# 1-Schematic_Automatic_watering_v1_1.net
KiCad netlist of a schematic drawn in EasyEDA
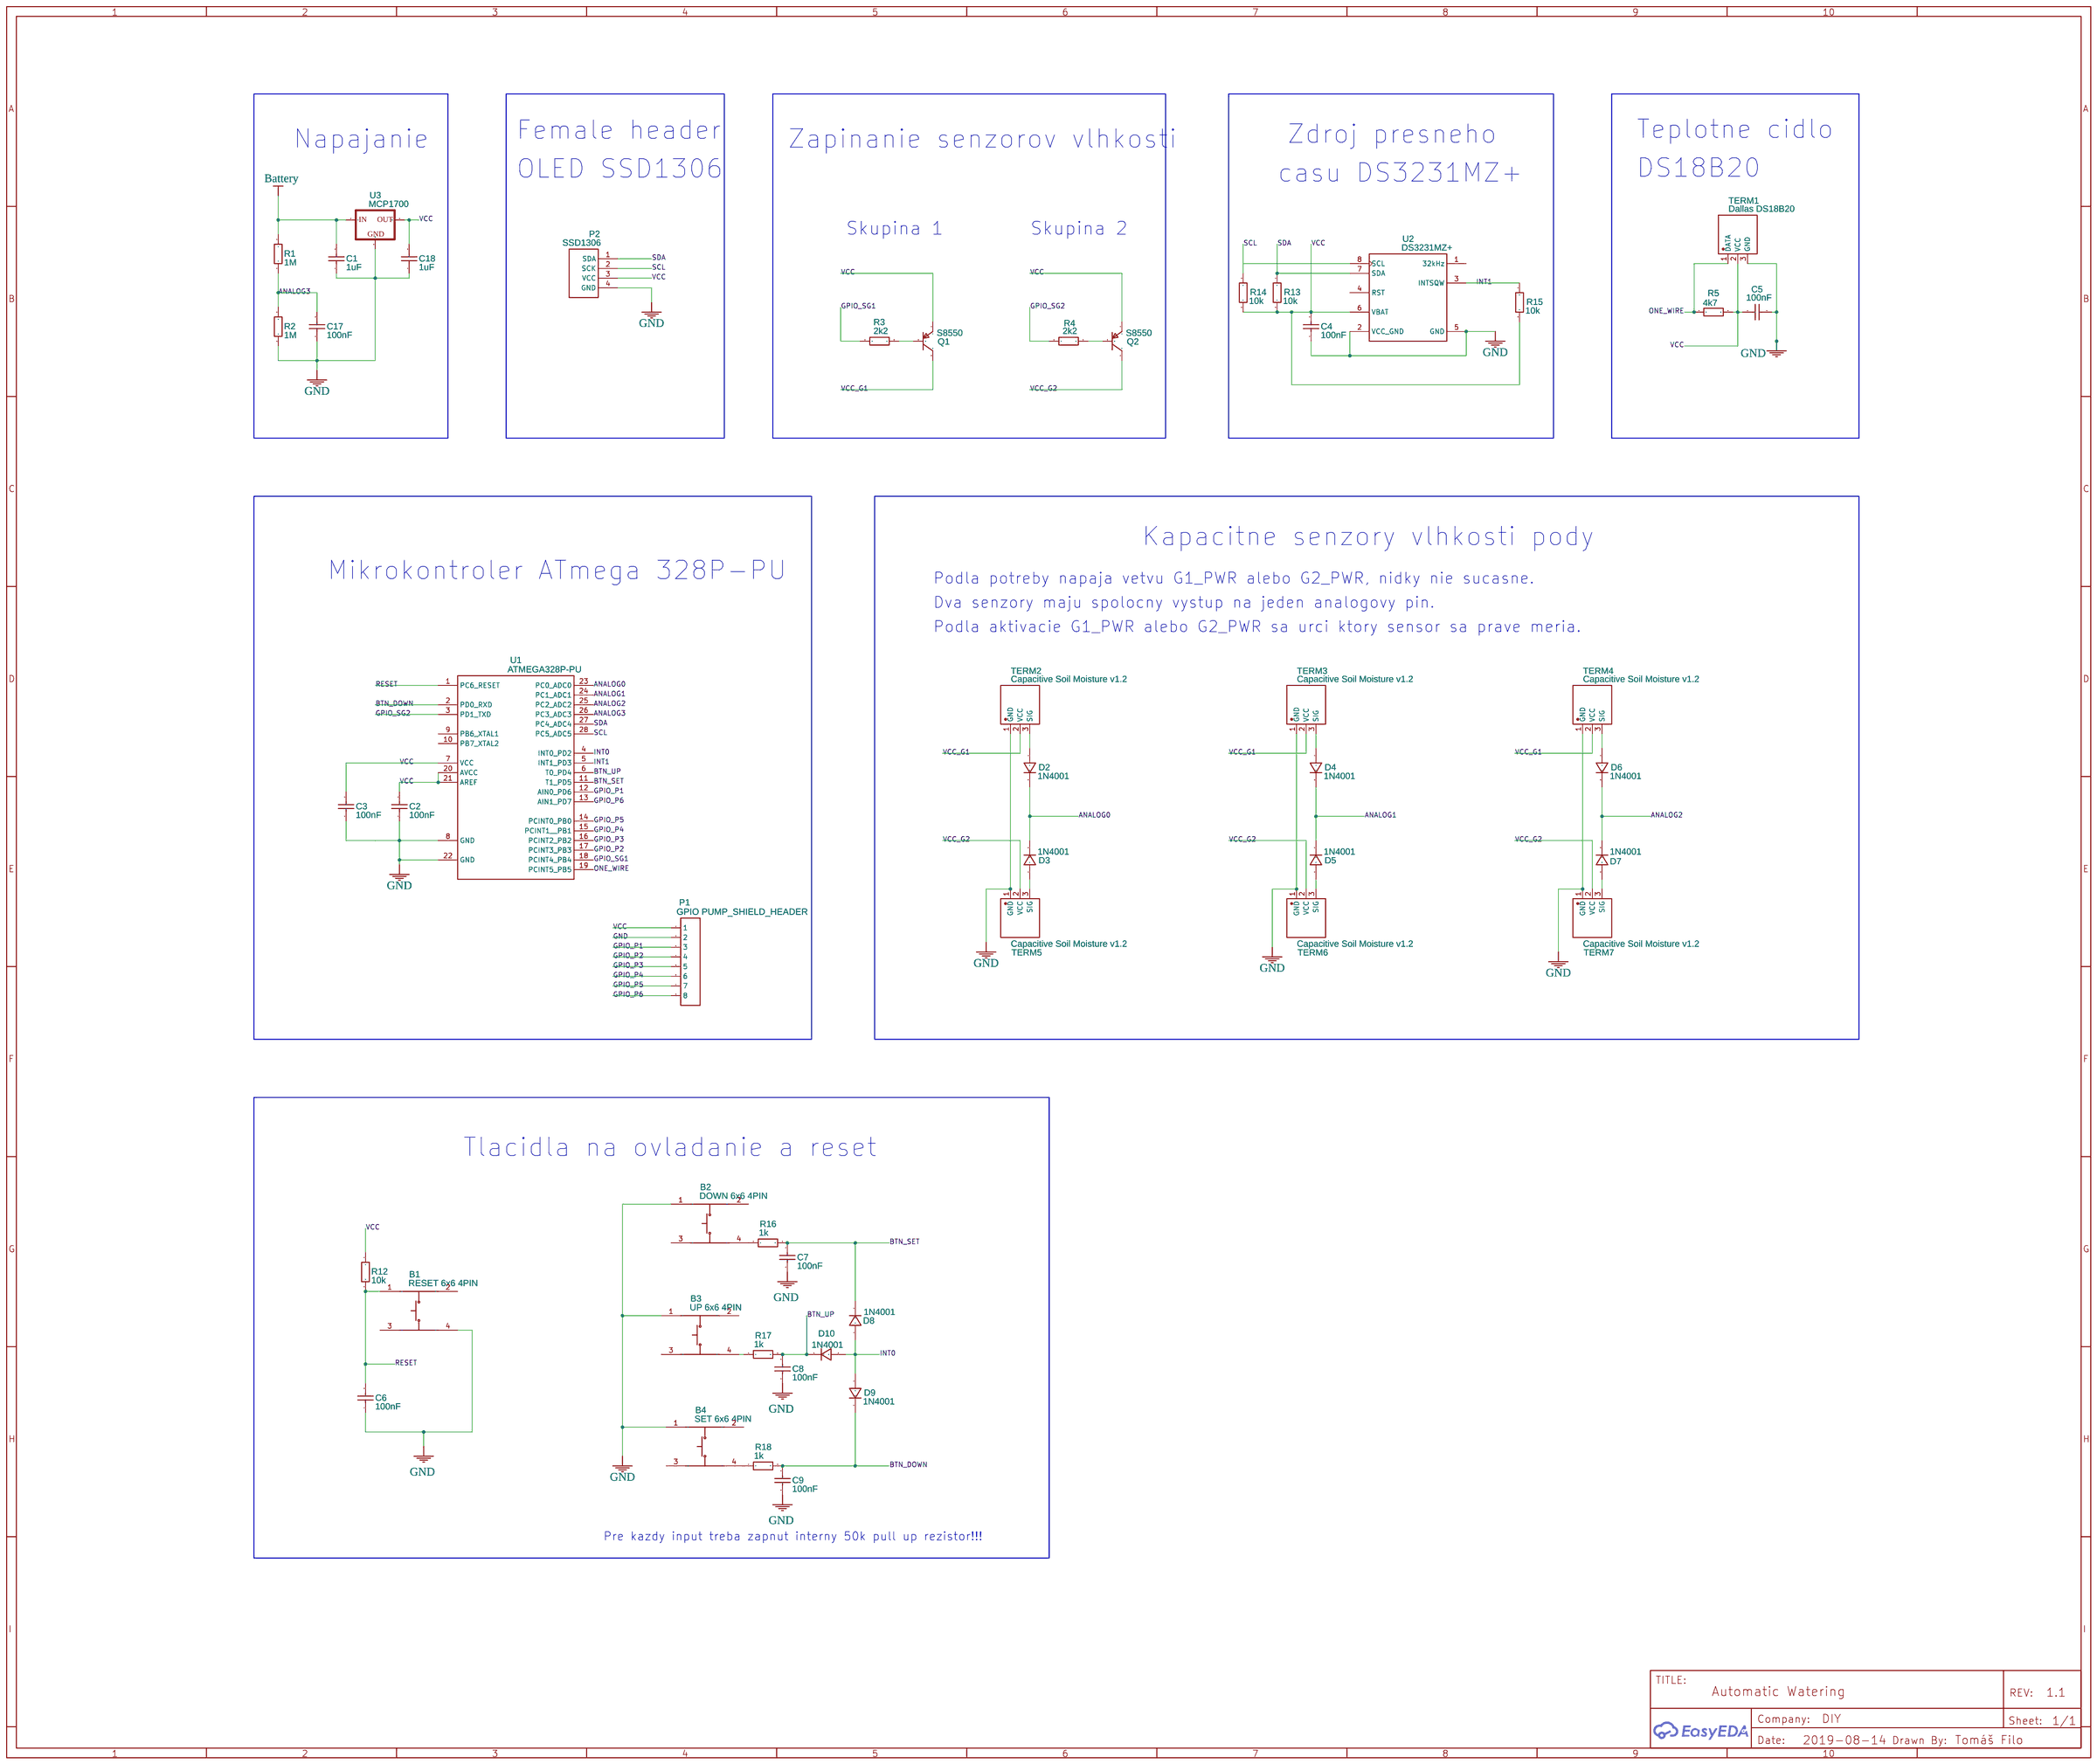
[diagram p0: schematic sheet]

(export (version "E")
  (design (tool "Eeschema 10.0.6"))
  (components
    (comp (ref "B1")
      (value "RESET 6x6 4PIN")
      (fields
        (field (name "BOM_Manufacturer Part") "TC-1102-C-E-B")
        (field (name "BOM_Supplier Part") "C381011")
      )
      (libsource (lib "") (part "Unknown_425_1345"))
    )
    (comp (ref "B2")
      (value "DOWN 6x6 4PIN")
      (fields
        (field (name "BOM_Manufacturer Part") "TC-1102-C-E-B")
        (field (name "BOM_Supplier Part") "C381011")
      )
      (libsource (lib "") (part "Unknown_725_1255"))
    )
    (comp (ref "B3")
      (value "UP 6x6 4PIN")
      (fields
        (field (name "BOM_Manufacturer Part") "TC-1102-C-E-B")
        (field (name "BOM_Supplier Part") "C381011")
      )
      (libsource (lib "") (part "Unknown_715_1370"))
    )
    (comp (ref "B4")
      (value "SET 6x6 4PIN")
      (fields
        (field (name "BOM_Manufacturer Part") "TC-1102-C-E-B")
        (field (name "BOM_Supplier Part") "C381011")
      )
      (libsource (lib "") (part "Unknown_720_1485"))
    )
    (comp (ref "C1")
      (value "1uF")
      (fields
        (field (name "BOM_Manufacturer Part") "CD1H224KC9BER1E000")
        (field (name "BOM_Supplier Part") "C263191")
      )
      (libsource (lib "") (part "CD1H224KC9BER1E000_1"))
    )
    (comp (ref "C2")
      (value "100nF")
      (fields
        (field (name "BOM_Manufacturer Part") "CD1H224KC9BER1E000")
        (field (name "BOM_Supplier Part") "C263191")
      )
      (libsource (lib "") (part "CD1H224KC9BER1E000_1"))
    )
    (comp (ref "C3")
      (value "100nF")
      (fields
        (field (name "BOM_Manufacturer Part") "CD1H224KC9BER1E000")
        (field (name "BOM_Supplier Part") "C263191")
      )
      (libsource (lib "") (part "CD1H224KC9BER1E000_1"))
    )
    (comp (ref "C4")
      (value "100nF")
      (fields
        (field (name "BOM_Manufacturer Part") "CD1H224KC9BER1E000")
        (field (name "BOM_Supplier Part") "C263191")
      )
      (libsource (lib "") (part "CD1H224KC9BER1E000_1"))
    )
    (comp (ref "C5")
      (value "100nF")
      (fields
        (field (name "BOM_Manufacturer Part") "CD1H224KC9BER1E000")
        (field (name "BOM_Supplier Part") "C263191")
      )
      (libsource (lib "") (part "CD1H224KC9BER1E000"))
    )
    (comp (ref "C6")
      (value "100nF")
      (fields
        (field (name "BOM_Manufacturer Part") "CD1H224KC9BER1E000")
        (field (name "BOM_Supplier Part") "C263191")
      )
      (libsource (lib "") (part "CD1H224KC9BER1E000_1"))
    )
    (comp (ref "C7")
      (value "100nF")
      (fields
        (field (name "BOM_Manufacturer Part") "CD1H224KC9BER1E000")
        (field (name "BOM_Supplier Part") "C263191")
      )
      (libsource (lib "") (part "CD1H224KC9BER1E000_1"))
    )
    (comp (ref "C8")
      (value "100nF")
      (fields
        (field (name "BOM_Manufacturer Part") "CD1H224KC9BER1E000")
        (field (name "BOM_Supplier Part") "C263191")
      )
      (libsource (lib "") (part "CD1H224KC9BER1E000_1"))
    )
    (comp (ref "C9")
      (value "100nF")
      (fields
        (field (name "BOM_Manufacturer Part") "CD1H224KC9BER1E000")
        (field (name "BOM_Supplier Part") "C263191")
      )
      (libsource (lib "") (part "CD1H224KC9BER1E000_1"))
    )
    (comp (ref "C17")
      (value "100nF")
      (fields
        (field (name "BOM_Manufacturer Part") "CD1H224KC9BER1E000")
        (field (name "BOM_Supplier Part") "C263191")
      )
      (libsource (lib "") (part "CD1H224KC9BER1E000_1"))
    )
    (comp (ref "C18")
      (value "1uF")
      (fields
        (field (name "BOM_Manufacturer Part") "CD1H224KC9BER1E000")
        (field (name "BOM_Supplier Part") "C263191")
      )
      (libsource (lib "") (part "CD1H224KC9BER1E000_1"))
    )
    (comp (ref "D2")
      (value "1N4001")
      (fields (field (name "BOM_Supplier Part") "C169150"))
      (libsource (lib "") (part "Unknown_1055_785"))
    )
    (comp (ref "D3")
      (value "1N4001")
      (fields (field (name "BOM_Supplier Part") "C169150"))
      (libsource (lib "") (part "Unknown_1055_880"))
    )
    (comp (ref "D4")
      (value "1N4001")
      (fields (field (name "BOM_Supplier Part") "C169150"))
      (libsource (lib "") (part "Unknown_1350_785"))
    )
    (comp (ref "D5")
      (value "1N4001")
      (fields (field (name "BOM_Supplier Part") "C169150"))
      (libsource (lib "") (part "Unknown_1350_880"))
    )
    (comp (ref "D6")
      (value "1N4001")
      (fields (field (name "BOM_Supplier Part") "C169150"))
      (libsource (lib "") (part "Unknown_1645_785"))
    )
    (comp (ref "D7")
      (value "1N4001")
      (fields (field (name "BOM_Supplier Part") "C169150"))
      (libsource (lib "") (part "Unknown_1645_880"))
    )
    (comp (ref "D8")
      (value "1N4001")
      (fields (field (name "BOM_Supplier Part") "C169150"))
      (libsource (lib "") (part "Unknown_875_1355"))
    )
    (comp (ref "D9")
      (value "1N4001")
      (fields (field (name "BOM_Supplier Part") "C169150"))
      (libsource (lib "") (part "Unknown_875_1430"))
    )
    (comp (ref "D10")
      (value "1N4001")
      (fields (field (name "BOM_Supplier Part") "C169150"))
      (libsource (lib "") (part "Unknown_845_1390"))
    )
    (comp (ref "P1")
      (value "GPIO PUMP_SHIELD_HEADER")
      (fields
        (field (name "BOM_Manufacturer Part") "Female headerHDR1X8-2.54")
        (field (name "BOM_Supplier Part") "C27438")
      )
      (libsource (lib "") (part "Unknown_700_985"))
    )
    (comp (ref "P2")
      (value "SSD1306")
      (fields
        (field (name "BOM_Manufacturer Part") "220S-1*4P H=8.5MM Ytype Gold-plated")
        (field (name "BOM_Supplier Part") "C124413")
      )
      (libsource (lib "") (part "Unknown_605_275"))
    )
    (comp (ref "Q1")
      (value "S8550")
      (fields (field (name "BOM_Manufacturer Part") "SS8550CTA") (field (name "BOM_Supplier Part") "C327518"))
      (libsource (lib "") (part "Unknown_945_345"))
    )
    (comp (ref "Q2")
      (value "S8550")
      (fields (field (name "BOM_Manufacturer Part") "SS8550CTA") (field (name "BOM_Supplier Part") "C327518"))
      (libsource (lib "") (part "Unknown_1140_345"))
    )
    (comp (ref "R1")
      (value "1M")
      (fields (field (name "BOM_Supplier Part") "C119320"))
      (libsource (lib "") (part "MF1/4W-680Ω±1% T52"))
    )
    (comp (ref "R2")
      (value "1M")
      (fields (field (name "BOM_Supplier Part") "C119320"))
      (libsource (lib "") (part "MF1/4W-680Ω±1% T52"))
    )
    (comp (ref "R3")
      (value "2k2")
      (fields (field (name "BOM_Supplier Part") "C119313"))
      (libsource (lib "") (part "MF1/4W-330Ω±1% T52_1"))
    )
    (comp (ref "R4")
      (value "2k2")
      (fields (field (name "BOM_Supplier Part") "C119313"))
      (libsource (lib "") (part "MF1/4W-330Ω±1% T52_1"))
    )
    (comp (ref "R5")
      (value "4k7")
      (fields (field (name "BOM_Supplier Part") "C119313"))
      (libsource (lib "") (part "MF1/4W-330Ω±1% T52_1"))
    )
    (comp (ref "R12")
      (value "10k")
      (fields (field (name "BOM_Supplier Part") "C119313"))
      (libsource (lib "") (part "MF1/4W-330Ω±1% T52"))
    )
    (comp (ref "R13")
      (value "10k")
      (fields (field (name "BOM_Supplier Part") "C119313"))
      (libsource (lib "") (part "MF1/4W-330Ω±1% T52"))
    )
    (comp (ref "R14")
      (value "10k")
      (fields (field (name "BOM_Supplier Part") "C119313"))
      (libsource (lib "") (part "MF1/4W-330Ω±1% T52"))
    )
    (comp (ref "R15")
      (value "10k")
      (fields (field (name "BOM_Supplier Part") "C119313"))
      (libsource (lib "") (part "MF1/4W-330Ω±1% T52"))
    )
    (comp (ref "R16")
      (value "1k")
      (fields (field (name "BOM_Supplier Part") "C119313"))
      (libsource (lib "") (part "MF1/4W-330Ω±1% T52_1"))
    )
    (comp (ref "R17")
      (value "1k")
      (fields (field (name "BOM_Supplier Part") "C119313"))
      (libsource (lib "") (part "MF1/4W-330Ω±1% T52_1"))
    )
    (comp (ref "R18")
      (value "1k")
      (fields (field (name "BOM_Supplier Part") "C119313"))
      (libsource (lib "") (part "MF1/4W-330Ω±1% T52_1"))
    )
    (comp (ref "TERM1")
      (value "Dallas DS18B20")
      (fields
        (field (name "BOM_Manufacturer Part") "EK500V-03P")
        (field (name "BOM_Supplier Part") "C182803")
      )
      (libsource (lib "") (part "Unknown_1785_240"))
    )
    (comp (ref "TERM2")
      (value "Capacitive Soil Moisture v1.2")
      (fields
        (field (name "BOM_Manufacturer Part") "EK500V-03P")
        (field (name "BOM_Supplier Part") "C182803")
      )
      (libsource (lib "") (part "Unknown_1045_725"))
    )
    (comp (ref "TERM3")
      (value "Capacitive Soil Moisture v1.2")
      (fields
        (field (name "BOM_Manufacturer Part") "EK500V-03P")
        (field (name "BOM_Supplier Part") "C182803")
      )
      (libsource (lib "") (part "Unknown_1340_725"))
    )
    (comp (ref "TERM4")
      (value "Capacitive Soil Moisture v1.2")
      (fields
        (field (name "BOM_Manufacturer Part") "EK500V-03P")
        (field (name "BOM_Supplier Part") "C182803")
      )
      (libsource (lib "") (part "Unknown_1635_725"))
    )
    (comp (ref "TERM5")
      (value "Capacitive Soil Moisture v1.2")
      (fields
        (field (name "BOM_Manufacturer Part") "EK500V-03P")
        (field (name "BOM_Supplier Part") "C182803")
      )
      (libsource (lib "") (part "Unknown_1045_935"))
    )
    (comp (ref "TERM6")
      (value "Capacitive Soil Moisture v1.2")
      (fields
        (field (name "BOM_Manufacturer Part") "EK500V-03P")
        (field (name "BOM_Supplier Part") "C182803")
      )
      (libsource (lib "") (part "Unknown_1340_935"))
    )
    (comp (ref "TERM7")
      (value "Capacitive Soil Moisture v1.2")
      (fields
        (field (name "BOM_Manufacturer Part") "EK500V-03P")
        (field (name "BOM_Supplier Part") "C182803")
      )
      (libsource (lib "") (part "Unknown_1635_935"))
    )
    (comp (ref "U1")
      (value "ATMEGA328P-PU")
      (fields (field (name "BOM_Supplier Part") "C33901"))
      (libsource (lib "") (part "Unknown_525_795"))
    )
    (comp (ref "U2")
      (value "DS3231MZ+")
      (fields (field (name "BOM_Supplier Part") "C107410"))
      (libsource (lib "") (part "Unknown_1445_300"))
    )
    (comp (ref "U3") (value "MCP1700") (libsource (lib "") (part "Unknown_380_230")))
  )
  (nets
    (net (code "1") (name "/ANALOG0") (class "Default")
      (node (ref "D2") (pin "2") (pinfunction "2_2") (pintype "unspecified"))
      (node (ref "D3") (pin "2") (pinfunction "2_2") (pintype "unspecified"))
      (node (ref "U1") (pin "23") (pinfunction "PC0_ADC0_23") (pintype "bidirectional"))
    )
    (net (code "2") (name "/ANALOG1") (class "Default")
      (node (ref "D4") (pin "2") (pinfunction "2_2") (pintype "unspecified"))
      (node (ref "D5") (pin "2") (pinfunction "2_2") (pintype "unspecified"))
      (node (ref "U1") (pin "24") (pinfunction "PC1_ADC1_24") (pintype "bidirectional"))
    )
    (net (code "3") (name "/ANALOG2") (class "Default")
      (node (ref "D6") (pin "2") (pinfunction "2_2") (pintype "unspecified"))
      (node (ref "D7") (pin "2") (pinfunction "2_2") (pintype "unspecified"))
      (node (ref "U1") (pin "25") (pinfunction "PC2_ADC2_25") (pintype "bidirectional"))
    )
    (net (code "4") (name "/ANALOG3") (class "Default")
      (node (ref "C17") (pin "2") (pinfunction "2_2") (pintype "input"))
      (node (ref "R1") (pin "2") (pinfunction "2_2") (pintype "unspecified"))
      (node (ref "R2") (pin "1") (pinfunction "1_1") (pintype "unspecified"))
      (node (ref "U1") (pin "26") (pinfunction "PC3_ADC3_26") (pintype "bidirectional"))
    )
    (net (code "5") (name "/BTN_DOWN") (class "Default")
      (node (ref "C9") (pin "2") (pinfunction "2_2") (pintype "input"))
      (node (ref "D9") (pin "2") (pinfunction "2_2") (pintype "unspecified"))
      (node (ref "R18") (pin "2") (pinfunction "2_2") (pintype "unspecified"))
      (node (ref "U1") (pin "2") (pinfunction "PD0_RXD_2") (pintype "bidirectional"))
    )
    (net (code "6") (name "/BTN_SET") (class "Default")
      (node (ref "C7") (pin "2") (pinfunction "2_2") (pintype "input"))
      (node (ref "D8") (pin "2") (pinfunction "2_2") (pintype "unspecified"))
      (node (ref "R16") (pin "2") (pinfunction "2_2") (pintype "unspecified"))
      (node (ref "U1") (pin "11") (pinfunction "T1_PD5_11") (pintype "bidirectional"))
    )
    (net (code "7") (name "/BTN_UP") (class "Default")
      (node (ref "C8") (pin "2") (pinfunction "2_2") (pintype "input"))
      (node (ref "D10") (pin "2") (pinfunction "2_2") (pintype "unspecified"))
      (node (ref "R17") (pin "2") (pinfunction "2_2") (pintype "unspecified"))
      (node (ref "U1") (pin "6") (pinfunction "T0_PD4_6") (pintype "bidirectional"))
    )
    (net (code "8") (name "/GPIO_P1") (class "Default")
      (node (ref "P1") (pin "3") (pinfunction "3_3") (pintype "input"))
      (node (ref "U1") (pin "12") (pinfunction "AIN0_PD6_12") (pintype "bidirectional"))
    )
    (net (code "9") (name "/GPIO_P2") (class "Default")
      (node (ref "P1") (pin "4") (pinfunction "4_4") (pintype "input"))
      (node (ref "U1") (pin "17") (pinfunction "PCINT3_PB3_17") (pintype "bidirectional"))
    )
    (net (code "10") (name "/GPIO_P3") (class "Default")
      (node (ref "P1") (pin "5") (pinfunction "5_5") (pintype "input"))
      (node (ref "U1") (pin "16") (pinfunction "PCINT2_PB2_16") (pintype "bidirectional"))
    )
    (net (code "11") (name "/GPIO_P4") (class "Default")
      (node (ref "P1") (pin "6") (pinfunction "6_6") (pintype "input"))
      (node (ref "U1") (pin "15") (pinfunction "PCINT1__PB1_15") (pintype "bidirectional"))
    )
    (net (code "12") (name "/GPIO_P5") (class "Default")
      (node (ref "P1") (pin "7") (pinfunction "7_7") (pintype "input"))
      (node (ref "U1") (pin "14") (pinfunction "PCINT0_PB0_14") (pintype "bidirectional"))
    )
    (net (code "13") (name "/GPIO_P6") (class "Default")
      (node (ref "P1") (pin "8") (pinfunction "8_8") (pintype "input"))
      (node (ref "U1") (pin "13") (pinfunction "AIN1_PD7_13") (pintype "bidirectional"))
    )
    (net (code "14") (name "/GPIO_SG1") (class "Default")
      (node (ref "R3") (pin "1") (pinfunction "1_1") (pintype "unspecified"))
      (node (ref "U1") (pin "18") (pinfunction "PCINT4_PB4_18") (pintype "bidirectional"))
    )
    (net (code "15") (name "/GPIO_SG2") (class "Default")
      (node (ref "R4") (pin "1") (pinfunction "1_1") (pintype "unspecified"))
      (node (ref "U1") (pin "3") (pinfunction "PD1_TXD_3") (pintype "bidirectional"))
    )
    (net (code "16") (name "/INT0") (class "Default")
      (node (ref "D10") (pin "1") (pinfunction "1_1") (pintype "unspecified"))
      (node (ref "D8") (pin "1") (pinfunction "1_1") (pintype "unspecified"))
      (node (ref "D9") (pin "1") (pinfunction "1_1") (pintype "unspecified"))
      (node (ref "U1") (pin "4") (pinfunction "INT0_PD2_4") (pintype "bidirectional"))
    )
    (net (code "17") (name "/INT1") (class "Default")
      (node (ref "R15") (pin "1") (pinfunction "1_1") (pintype "unspecified"))
      (node (ref "U1") (pin "5") (pinfunction "INT1_PD3_5") (pintype "bidirectional"))
      (node (ref "U2") (pin "3") (pinfunction "INTSQW_3") (pintype "bidirectional"))
    )
    (net (code "18") (name "/ONE_WIRE") (class "Default")
      (node (ref "R5") (pin "1") (pinfunction "1_1") (pintype "unspecified"))
      (node (ref "TERM1") (pin "1") (pinfunction "DATA_1") (pintype "unspecified"))
      (node (ref "U1") (pin "19") (pinfunction "PCINT5_PB5_19") (pintype "bidirectional"))
    )
    (net (code "19") (name "/RESET") (class "Default")
      (node (ref "B1") (pin "1") (pinfunction "1_1") (pintype "unspecified"))
      (node (ref "C6") (pin "2") (pinfunction "2_2") (pintype "input"))
      (node (ref "R12") (pin "2") (pinfunction "2_2") (pintype "unspecified"))
      (node (ref "U1") (pin "1") (pinfunction "PC6_RESET_1") (pintype "bidirectional"))
    )
    (net (code "20") (name "/SCL") (class "Default")
      (node (ref "P2") (pin "2") (pinfunction "SCK_2") (pintype "unspecified"))
      (node (ref "R14") (pin "1") (pinfunction "1_1") (pintype "unspecified"))
      (node (ref "U1") (pin "28") (pinfunction "PC5_ADC5_28") (pintype "bidirectional"))
      (node (ref "U2") (pin "8") (pinfunction "SCL_8") (pintype "unspecified"))
    )
    (net (code "21") (name "/SDA") (class "Default")
      (node (ref "P2") (pin "1") (pinfunction "SDA_1") (pintype "unspecified"))
      (node (ref "R13") (pin "1") (pinfunction "1_1") (pintype "unspecified"))
      (node (ref "U1") (pin "27") (pinfunction "PC4_ADC4_27") (pintype "bidirectional"))
      (node (ref "U2") (pin "7") (pinfunction "SDA_7") (pintype "bidirectional"))
    )
    (net (code "22") (name "/VCC") (class "Default")
      (node (ref "C18") (pin "2") (pinfunction "2_2") (pintype "input"))
      (node (ref "C2") (pin "2") (pinfunction "2_2") (pintype "input"))
      (node (ref "C3") (pin "2") (pinfunction "2_2") (pintype "input"))
      (node (ref "C4") (pin "2") (pinfunction "2_2") (pintype "input"))
      (node (ref "C5") (pin "1") (pinfunction "1_1") (pintype "input"))
      (node (ref "P1") (pin "1") (pinfunction "1_1") (pintype "input"))
      (node (ref "P2") (pin "3") (pinfunction "VCC_3") (pintype "unspecified"))
      (node (ref "Q1") (pin "1") (pinfunction "E_1") (pintype "unspecified"))
      (node (ref "Q2") (pin "1") (pinfunction "E_1") (pintype "unspecified"))
      (node (ref "R12") (pin "1") (pinfunction "1_1") (pintype "unspecified"))
      (node (ref "R13") (pin "2") (pinfunction "2_2") (pintype "unspecified"))
      (node (ref "R14") (pin "2") (pinfunction "2_2") (pintype "unspecified"))
      (node (ref "R15") (pin "2") (pinfunction "2_2") (pintype "unspecified"))
      (node (ref "R5") (pin "2") (pinfunction "2_2") (pintype "unspecified"))
      (node (ref "TERM1") (pin "2") (pinfunction "VCC_2") (pintype "unspecified"))
      (node (ref "U1") (pin "20") (pinfunction "AVCC_20") (pintype "passive"))
      (node (ref "U1") (pin "21") (pinfunction "AREF_21") (pintype "passive"))
      (node (ref "U1") (pin "7") (pinfunction "VCC_7") (pintype "passive"))
      (node (ref "U2") (pin "6") (pinfunction "VBAT_6") (pintype "passive"))
      (node (ref "U3") (pin "3") (pinfunction "OUT_3") (pintype "unspecified"))
    )
    (net (code "23") (name "/VCC_G1") (class "Default")
      (node (ref "Q1") (pin "3") (pinfunction "C_3") (pintype "unspecified"))
      (node (ref "TERM2") (pin "2") (pinfunction "VCC_2") (pintype "unspecified"))
      (node (ref "TERM3") (pin "2") (pinfunction "VCC_2") (pintype "unspecified"))
      (node (ref "TERM4") (pin "2") (pinfunction "VCC_2") (pintype "unspecified"))
    )
    (net (code "24") (name "/VCC_G2") (class "Default")
      (node (ref "Q2") (pin "3") (pinfunction "C_3") (pintype "unspecified"))
      (node (ref "TERM5") (pin "2") (pinfunction "VCC_2") (pintype "unspecified"))
      (node (ref "TERM6") (pin "2") (pinfunction "VCC_2") (pintype "unspecified"))
      (node (ref "TERM7") (pin "2") (pinfunction "VCC_2") (pintype "unspecified"))
    )
    (net (code "25") (name "Battery") (class "Default")
      (node (ref "C1") (pin "2") (pinfunction "2_2") (pintype "input"))
      (node (ref "R1") (pin "1") (pinfunction "1_1") (pintype "unspecified"))
      (node (ref "U3") (pin "2") (pinfunction "IN_2") (pintype "input"))
    )
    (net (code "26") (name "GND") (class "Default")
      (node (ref "B1") (pin "4") (pinfunction "4_4") (pintype "unspecified"))
      (node (ref "B2") (pin "1") (pinfunction "1_1") (pintype "unspecified"))
      (node (ref "B3") (pin "1") (pinfunction "1_1") (pintype "unspecified"))
      (node (ref "B4") (pin "1") (pinfunction "1_1") (pintype "unspecified"))
      (node (ref "C1") (pin "1") (pinfunction "1_1") (pintype "input"))
      (node (ref "C17") (pin "1") (pinfunction "1_1") (pintype "input"))
      (node (ref "C18") (pin "1") (pinfunction "1_1") (pintype "input"))
      (node (ref "C2") (pin "1") (pinfunction "1_1") (pintype "input"))
      (node (ref "C3") (pin "1") (pinfunction "1_1") (pintype "input"))
      (node (ref "C4") (pin "1") (pinfunction "1_1") (pintype "input"))
      (node (ref "C5") (pin "2") (pinfunction "2_2") (pintype "input"))
      (node (ref "C6") (pin "1") (pinfunction "1_1") (pintype "input"))
      (node (ref "C7") (pin "1") (pinfunction "1_1") (pintype "input"))
      (node (ref "C8") (pin "1") (pinfunction "1_1") (pintype "input"))
      (node (ref "C9") (pin "1") (pinfunction "1_1") (pintype "input"))
      (node (ref "P1") (pin "2") (pinfunction "2_2") (pintype "input"))
      (node (ref "P2") (pin "4") (pinfunction "GND_4") (pintype "unspecified"))
      (node (ref "R2") (pin "2") (pinfunction "2_2") (pintype "unspecified"))
      (node (ref "TERM1") (pin "3") (pinfunction "GND_3") (pintype "unspecified"))
      (node (ref "TERM2") (pin "1") (pinfunction "GND_1") (pintype "unspecified"))
      (node (ref "TERM3") (pin "1") (pinfunction "GND_1") (pintype "unspecified"))
      (node (ref "TERM4") (pin "1") (pinfunction "GND_1") (pintype "unspecified"))
      (node (ref "TERM5") (pin "1") (pinfunction "GND_1") (pintype "unspecified"))
      (node (ref "TERM6") (pin "1") (pinfunction "GND_1") (pintype "unspecified"))
      (node (ref "TERM7") (pin "1") (pinfunction "GND_1") (pintype "unspecified"))
      (node (ref "U1") (pin "22") (pinfunction "GND_22") (pintype "passive"))
      (node (ref "U1") (pin "8") (pinfunction "GND_8") (pintype "passive"))
      (node (ref "U2") (pin "2") (pinfunction "VCC_GND_2") (pintype "passive"))
      (node (ref "U2") (pin "5") (pinfunction "GND_5") (pintype "passive"))
      (node (ref "U3") (pin "1") (pinfunction "GND_1") (pintype "input"))
    )
    (net (code "27") (name "Net-(B2-Pad4)") (class "Default")
      (node (ref "B2") (pin "4") (pinfunction "4_4") (pintype "unspecified"))
      (node (ref "R16") (pin "1") (pinfunction "1_1") (pintype "unspecified"))
    )
    (net (code "28") (name "Net-(B3-Pad4)") (class "Default")
      (node (ref "B3") (pin "4") (pinfunction "4_4") (pintype "unspecified"))
      (node (ref "R17") (pin "1") (pinfunction "1_1") (pintype "unspecified"))
    )
    (net (code "29") (name "Net-(B4-Pad4)") (class "Default")
      (node (ref "B4") (pin "4") (pinfunction "4_4") (pintype "unspecified"))
      (node (ref "R18") (pin "1") (pinfunction "1_1") (pintype "unspecified"))
    )
    (net (code "30") (name "Net-(Q1-B)") (class "Default")
      (node (ref "Q1") (pin "2") (pinfunction "B_2") (pintype "unspecified"))
      (node (ref "R3") (pin "2") (pinfunction "2_2") (pintype "unspecified"))
    )
    (net (code "31") (name "Net-(Q2-B)") (class "Default")
      (node (ref "Q2") (pin "2") (pinfunction "B_2") (pintype "unspecified"))
      (node (ref "R4") (pin "2") (pinfunction "2_2") (pintype "unspecified"))
    )
    (net (code "32") (name "Net-(TERM2-SIG)") (class "Default")
      (node (ref "D2") (pin "1") (pinfunction "1_1") (pintype "unspecified"))
      (node (ref "TERM2") (pin "3") (pinfunction "SIG_3") (pintype "unspecified"))
    )
    (net (code "33") (name "Net-(TERM3-SIG)") (class "Default")
      (node (ref "D4") (pin "1") (pinfunction "1_1") (pintype "unspecified"))
      (node (ref "TERM3") (pin "3") (pinfunction "SIG_3") (pintype "unspecified"))
    )
    (net (code "34") (name "Net-(TERM4-SIG)") (class "Default")
      (node (ref "D6") (pin "1") (pinfunction "1_1") (pintype "unspecified"))
      (node (ref "TERM4") (pin "3") (pinfunction "SIG_3") (pintype "unspecified"))
    )
    (net (code "35") (name "Net-(TERM5-SIG)") (class "Default")
      (node (ref "D3") (pin "1") (pinfunction "1_1") (pintype "unspecified"))
      (node (ref "TERM5") (pin "3") (pinfunction "SIG_3") (pintype "unspecified"))
    )
    (net (code "36") (name "Net-(TERM6-SIG)") (class "Default")
      (node (ref "D5") (pin "1") (pinfunction "1_1") (pintype "unspecified"))
      (node (ref "TERM6") (pin "3") (pinfunction "SIG_3") (pintype "unspecified"))
    )
    (net (code "37") (name "Net-(TERM7-SIG)") (class "Default")
      (node (ref "D7") (pin "1") (pinfunction "1_1") (pintype "unspecified"))
      (node (ref "TERM7") (pin "3") (pinfunction "SIG_3") (pintype "unspecified"))
    )
    (net (code "38") (name "unconnected-(B1-Pad2)") (class "Default")
      (node (ref "B1") (pin "2") (pinfunction "2_2") (pintype "unspecified"))
    )
    (net (code "39") (name "unconnected-(B1-Pad3)") (class "Default")
      (node (ref "B1") (pin "3") (pinfunction "3_3") (pintype "unspecified"))
    )
    (net (code "40") (name "unconnected-(B2-Pad2)") (class "Default")
      (node (ref "B2") (pin "2") (pinfunction "2_2") (pintype "unspecified"))
    )
    (net (code "41") (name "unconnected-(B2-Pad3)") (class "Default")
      (node (ref "B2") (pin "3") (pinfunction "3_3") (pintype "unspecified"))
    )
    (net (code "42") (name "unconnected-(B3-Pad2)") (class "Default")
      (node (ref "B3") (pin "2") (pinfunction "2_2") (pintype "unspecified"))
    )
    (net (code "43") (name "unconnected-(B3-Pad3)") (class "Default")
      (node (ref "B3") (pin "3") (pinfunction "3_3") (pintype "unspecified"))
    )
    (net (code "44") (name "unconnected-(B4-Pad2)") (class "Default")
      (node (ref "B4") (pin "2") (pinfunction "2_2") (pintype "unspecified"))
    )
    (net (code "45") (name "unconnected-(B4-Pad3)") (class "Default")
      (node (ref "B4") (pin "3") (pinfunction "3_3") (pintype "unspecified"))
    )
    (net (code "46") (name "unconnected-(U1-PB6_XTAL1-Pad9)") (class "Default")
      (node (ref "U1") (pin "9") (pinfunction "PB6_XTAL1_9") (pintype "bidirectional"))
    )
    (net (code "47") (name "unconnected-(U1-PB7_XTAL2-Pad10)") (class "Default")
      (node (ref "U1") (pin "10") (pinfunction "PB7_XTAL2_10") (pintype "bidirectional"))
    )
    (net (code "48") (name "unconnected-(U2-32kHz-Pad1)") (class "Default")
      (node (ref "U2") (pin "1") (pinfunction "32kHz_1") (pintype "unspecified"))
    )
    (net (code "49") (name "unconnected-(U2-RST-Pad4)") (class "Default")
      (node (ref "U2") (pin "4") (pinfunction "RST_4") (pintype "bidirectional"))
    )
  )
)
